# teensy_sync_rev1.net
KiCad netlist of a schematic drawn in EAGLE
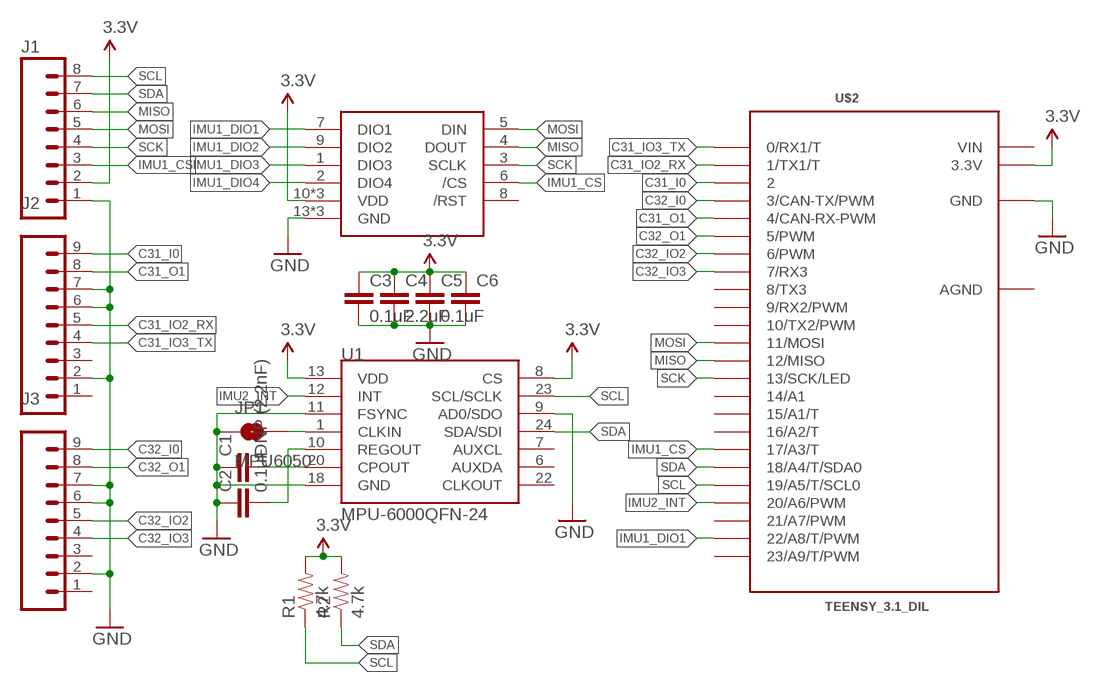
[diagram p0: schematic, sheet 1]

(export (version "E")
  (design (tool "Eeschema 10.0.6"))
  (components
    (comp (ref "C1")
      (value "DNP (2.2nF)")
      (footprint "eagle-import:0402-CAP")
      (libsource (lib "eagle-import") (part "CAP0402-CAP"))
    )
    (comp (ref "C2")
      (value "0.1uF")
      (footprint "eagle-import:0402-CAP")
      (libsource (lib "eagle-import") (part "CAP0402-CAP"))
    )
    (comp (ref "C3")
      (value "0.1uF")
      (footprint "eagle-import:0402-CAP")
      (libsource (lib "eagle-import") (part "CAP0402-CAP"))
    )
    (comp (ref "C4")
      (value "2.2uF")
      (footprint "eagle-import:0402-CAP")
      (libsource (lib "eagle-import") (part "CAP0402-CAP"))
    )
    (comp (ref "C5")
      (value "0.1uF")
      (footprint "eagle-import:0402-CAP")
      (libsource (lib "eagle-import") (part "CAP0402-CAP"))
    )
    (comp (ref "C6")
      (value "CAP0402-CAP")
      (footprint "eagle-import:0402-CAP")
      (libsource (lib "eagle-import") (part "CAP0402-CAP"))
    )
    (comp (ref "J1")
      (value "M08")
      (footprint "eagle-import:1X08_ROUND")
      (libsource (lib "eagle-import") (part "M08"))
    )
    (comp (ref "J2")
      (value "M09")
      (footprint "eagle-import:1X09")
      (libsource (lib "eagle-import") (part "M09"))
    )
    (comp (ref "J3")
      (value "M09")
      (footprint "eagle-import:1X09")
      (libsource (lib "eagle-import") (part "M09"))
    )
    (comp (ref "JP1")
      (value "MPU6050")
      (footprint "eagle-import:PAD-JUMPER-2-NO_YES_SILK")
      (libsource (lib "eagle-import") (part "JUMPER-PAD-2-NOYES_SILK"))
    )
    (comp (ref "R1")
      (value "4.7k")
      (footprint "eagle-import:0603-RES")
      (libsource (lib "eagle-import") (part "RESISTOR0603"))
    )
    (comp (ref "R2")
      (value "4.7k")
      (footprint "eagle-import:0603-RES")
      (libsource (lib "eagle-import") (part "RESISTOR0603"))
    )
    (comp (ref "U$1")
      (value "ADIS16448")
      (footprint "eagle-import:ADIS16448")
      (libsource (lib "eagle-import") (part "ADIS16448"))
    )
    (comp (ref "U$2")
      (value "TEENSY_3.1_DIL")
      (footprint "eagle-import:TEENSY3-DIL")
      (libsource (lib "eagle-import") (part "TEENSY_3.1_DIL"))
    )
    (comp (ref "U1")
      (value "MPU-6000QFN-24")
      (footprint "eagle-import:QFN-24-TESTING")
      (libsource (lib "eagle-import") (part "MPU-6000QFN-24"))
    )
  )
  (nets
    (net (code "1") (name "/AGND") (class "Default")
      (node (ref "U$2") (pin "AGND") (pinfunction "AGND_AGND") (pintype "power_in"))
    )
    (net (code "2") (name "/VIN") (class "Default")
      (node (ref "U$2") (pin "VIN") (pinfunction "VIN_VIN") (pintype "power_in"))
    )
    (net (code "3") (name "3.3V") (class "Default")
      (node (ref "C3") (pin "1") (pinfunction "1_1") (pintype "passive"))
      (node (ref "C4") (pin "1") (pinfunction "1_1") (pintype "passive"))
      (node (ref "C5") (pin "1") (pinfunction "1_1") (pintype "passive"))
      (node (ref "C6") (pin "1") (pinfunction "1_1") (pintype "passive"))
      (node (ref "J1") (pin "2") (pinfunction "2_2") (pintype "passive"))
      (node (ref "R1") (pin "2") (pinfunction "2_2") (pintype "passive"))
      (node (ref "R2") (pin "2") (pinfunction "2_2") (pintype "passive"))
      (node (ref "U$1") (pin "10") (pinfunction "VDD_10") (pintype "bidirectional"))
      (node (ref "U$1") (pin "11") (pinfunction "VDD_11") (pintype "bidirectional"))
      (node (ref "U$1") (pin "12") (pinfunction "VDD_12") (pintype "bidirectional"))
      (node (ref "U$2") (pin "3.3V") (pinfunction "3.3V_3.3V") (pintype "power_in"))
      (node (ref "U1") (pin "13") (pinfunction "VDD_13") (pintype "bidirectional"))
      (node (ref "U1") (pin "8") (pinfunction "CS_8") (pintype "bidirectional"))
    )
    (net (code "4") (name "C31_I0") (class "Default")
      (node (ref "J2") (pin "9") (pinfunction "9_9") (pintype "passive"))
      (node (ref "U$2") (pin "2") (pinfunction "2_2") (pintype "bidirectional"))
    )
    (net (code "5") (name "C31_IO2_RX") (class "Default")
      (node (ref "J2") (pin "5") (pinfunction "5_5") (pintype "passive"))
      (node (ref "U$2") (pin "1") (pinfunction "1/TX1/T_1") (pintype "bidirectional"))
    )
    (net (code "6") (name "C31_IO3_TX") (class "Default")
      (node (ref "J2") (pin "4") (pinfunction "4_4") (pintype "passive"))
      (node (ref "U$2") (pin "0") (pinfunction "0/RX1/T_0") (pintype "bidirectional"))
    )
    (net (code "7") (name "C31_O1") (class "Default")
      (node (ref "J2") (pin "8") (pinfunction "8_8") (pintype "passive"))
      (node (ref "U$2") (pin "4") (pinfunction "4/CAN-RX-PWM_4") (pintype "bidirectional"))
    )
    (net (code "8") (name "C32_I0") (class "Default")
      (node (ref "J3") (pin "9") (pinfunction "9_9") (pintype "passive"))
      (node (ref "U$2") (pin "3") (pinfunction "3/CAN-TX/PWM_3") (pintype "bidirectional"))
    )
    (net (code "9") (name "C32_IO2") (class "Default")
      (node (ref "J3") (pin "5") (pinfunction "5_5") (pintype "passive"))
      (node (ref "U$2") (pin "6") (pinfunction "6/PWM_6") (pintype "bidirectional"))
    )
    (net (code "10") (name "C32_IO3") (class "Default")
      (node (ref "J3") (pin "4") (pinfunction "4_4") (pintype "passive"))
      (node (ref "U$2") (pin "7") (pinfunction "7/RX3_7") (pintype "bidirectional"))
    )
    (net (code "11") (name "C32_O1") (class "Default")
      (node (ref "J3") (pin "8") (pinfunction "8_8") (pintype "passive"))
      (node (ref "U$2") (pin "5") (pinfunction "5/PWM_5") (pintype "bidirectional"))
    )
    (net (code "12") (name "GND") (class "Default")
      (node (ref "C1") (pin "1") (pinfunction "1_1") (pintype "passive"))
      (node (ref "C2") (pin "1") (pinfunction "1_1") (pintype "passive"))
      (node (ref "C3") (pin "2") (pinfunction "2_2") (pintype "passive"))
      (node (ref "C4") (pin "2") (pinfunction "2_2") (pintype "passive"))
      (node (ref "C5") (pin "2") (pinfunction "2_2") (pintype "passive"))
      (node (ref "C6") (pin "2") (pinfunction "2_2") (pintype "passive"))
      (node (ref "J1") (pin "1") (pinfunction "1_1") (pintype "passive"))
      (node (ref "J2") (pin "2") (pinfunction "2_2") (pintype "passive"))
      (node (ref "J2") (pin "6") (pinfunction "6_6") (pintype "passive"))
      (node (ref "J2") (pin "7") (pinfunction "7_7") (pintype "passive"))
      (node (ref "J3") (pin "2") (pinfunction "2_2") (pintype "passive"))
      (node (ref "J3") (pin "6") (pinfunction "6_6") (pintype "passive"))
      (node (ref "J3") (pin "7") (pinfunction "7_7") (pintype "passive"))
      (node (ref "JP1") (pin "1") (pinfunction "1_1") (pintype "passive"))
      (node (ref "U$1") (pin "13") (pinfunction "GND_13") (pintype "bidirectional"))
      (node (ref "U$1") (pin "14") (pinfunction "GND_14") (pintype "bidirectional"))
      (node (ref "U$1") (pin "15") (pinfunction "GND_15") (pintype "bidirectional"))
      (node (ref "U$2") (pin "GND") (pinfunction "GND_GND") (pintype "power_in"))
      (node (ref "U1") (pin "11") (pinfunction "FSYNC_11") (pintype "bidirectional"))
      (node (ref "U1") (pin "18") (pinfunction "GND_18") (pintype "bidirectional"))
      (node (ref "U1") (pin "9") (pinfunction "AD0/SDO_9") (pintype "bidirectional"))
    )
    (net (code "13") (name "IMU1_CS") (class "Default")
      (node (ref "J1") (pin "3") (pinfunction "3_3") (pintype "passive"))
      (node (ref "U$1") (pin "6") (pinfunction "/CS_6") (pintype "bidirectional"))
      (node (ref "U$2") (pin "17/A3") (pinfunction "17/A3/T_17/A3") (pintype "bidirectional"))
    )
    (net (code "14") (name "IMU1_DIO1") (class "Default")
      (node (ref "U$1") (pin "7") (pinfunction "DIO1_7") (pintype "bidirectional"))
      (node (ref "U$2") (pin "22/A8") (pinfunction "22/A8/T/PWM_22/A8") (pintype "bidirectional"))
    )
    (net (code "15") (name "IMU1_DIO2") (class "Default")
      (node (ref "U$1") (pin "9") (pinfunction "DIO2_9") (pintype "bidirectional"))
    )
    (net (code "16") (name "IMU1_DIO3") (class "Default")
      (node (ref "U$1") (pin "1") (pinfunction "DIO3_1") (pintype "bidirectional"))
    )
    (net (code "17") (name "IMU1_DIO4") (class "Default")
      (node (ref "U$1") (pin "2") (pinfunction "DIO4_2") (pintype "bidirectional"))
    )
    (net (code "18") (name "IMU2_INT") (class "Default")
      (node (ref "U$2") (pin "20/A6") (pinfunction "20/A6/PWM_20/A6") (pintype "bidirectional"))
      (node (ref "U1") (pin "12") (pinfunction "INT_12") (pintype "bidirectional"))
    )
    (net (code "19") (name "MISO") (class "Default")
      (node (ref "J1") (pin "6") (pinfunction "6_6") (pintype "passive"))
      (node (ref "U$1") (pin "4") (pinfunction "DOUT_4") (pintype "bidirectional"))
      (node (ref "U$2") (pin "12") (pinfunction "12/MISO_12") (pintype "bidirectional"))
    )
    (net (code "20") (name "MOSI") (class "Default")
      (node (ref "J1") (pin "5") (pinfunction "5_5") (pintype "passive"))
      (node (ref "U$1") (pin "5") (pinfunction "DIN_5") (pintype "bidirectional"))
      (node (ref "U$2") (pin "11") (pinfunction "11/MOSI_11") (pintype "bidirectional"))
    )
    (net (code "21") (name "Net-(U1-CLKIN)") (class "Default")
      (node (ref "JP1") (pin "2") (pinfunction "2_2") (pintype "passive"))
      (node (ref "U1") (pin "1") (pinfunction "CLKIN_1") (pintype "bidirectional"))
    )
    (net (code "22") (name "Net-(U1-CPOUT)") (class "Default")
      (node (ref "C1") (pin "2") (pinfunction "2_2") (pintype "passive"))
      (node (ref "U1") (pin "20") (pinfunction "CPOUT_20") (pintype "bidirectional"))
    )
    (net (code "23") (name "Net-(U1-REGOUT)") (class "Default")
      (node (ref "C2") (pin "2") (pinfunction "2_2") (pintype "passive"))
      (node (ref "U1") (pin "10") (pinfunction "REGOUT_10") (pintype "bidirectional"))
    )
    (net (code "24") (name "SCK") (class "Default")
      (node (ref "J1") (pin "4") (pinfunction "4_4") (pintype "passive"))
      (node (ref "U$1") (pin "3") (pinfunction "SCLK_3") (pintype "bidirectional"))
      (node (ref "U$2") (pin "13") (pinfunction "13/SCK/LED_13") (pintype "bidirectional"))
    )
    (net (code "25") (name "SCL") (class "Default")
      (node (ref "J1") (pin "8") (pinfunction "8_8") (pintype "passive"))
      (node (ref "R1") (pin "1") (pinfunction "1_1") (pintype "passive"))
      (node (ref "U$2") (pin "19/A5") (pinfunction "19/A5/T/SCL0_19/A5") (pintype "bidirectional"))
      (node (ref "U1") (pin "23") (pinfunction "SCL/SCLK_23") (pintype "bidirectional"))
    )
    (net (code "26") (name "SDA") (class "Default")
      (node (ref "J1") (pin "7") (pinfunction "7_7") (pintype "passive"))
      (node (ref "R2") (pin "1") (pinfunction "1_1") (pintype "passive"))
      (node (ref "U$2") (pin "18/A4") (pinfunction "18/A4/T/SDA0_18/A4") (pintype "bidirectional"))
      (node (ref "U1") (pin "24") (pinfunction "SDA/SDI_24") (pintype "bidirectional"))
    )
    (net (code "27") (name "unconnected-(J2-Pad1)") (class "Default")
      (node (ref "J2") (pin "1") (pinfunction "1_1") (pintype "passive"))
    )
    (net (code "28") (name "unconnected-(J2-Pad3)") (class "Default")
      (node (ref "J2") (pin "3") (pinfunction "3_3") (pintype "passive"))
    )
    (net (code "29") (name "unconnected-(J3-Pad1)") (class "Default")
      (node (ref "J3") (pin "1") (pinfunction "1_1") (pintype "passive"))
    )
    (net (code "30") (name "unconnected-(J3-Pad3)") (class "Default")
      (node (ref "J3") (pin "3") (pinfunction "3_3") (pintype "passive"))
    )
    (net (code "31") (name "unconnected-(U$1-{slash}RST-Pad8)") (class "Default")
      (node (ref "U$1") (pin "8") (pinfunction "/RST_8") (pintype "bidirectional"))
    )
    (net (code "32") (name "unconnected-(U$2-8{slash}TX3-Pad8)") (class "Default")
      (node (ref "U$2") (pin "8") (pinfunction "8/TX3_8") (pintype "bidirectional"))
    )
    (net (code "33") (name "unconnected-(U$2-9{slash}RX2{slash}PWM-Pad9)") (class "Default")
      (node (ref "U$2") (pin "9") (pinfunction "9/RX2/PWM_9") (pintype "bidirectional"))
    )
    (net (code "34") (name "unconnected-(U$2-10{slash}TX2{slash}PWM-Pad10)") (class "Default")
      (node (ref "U$2") (pin "10") (pinfunction "10/TX2/PWM_10") (pintype "bidirectional"))
    )
    (net (code "35") (name "unconnected-(U$2-14{slash}A1-Pad14{slash}A0)") (class "Default")
      (node (ref "U$2") (pin "14/A0") (pinfunction "14/A1_14/A0") (pintype "bidirectional"))
    )
    (net (code "36") (name "unconnected-(U$2-15{slash}A1{slash}T-Pad15{slash}A1)") (class "Default")
      (node (ref "U$2") (pin "15/A1") (pinfunction "15/A1/T_15/A1") (pintype "bidirectional"))
    )
    (net (code "37") (name "unconnected-(U$2-16{slash}A2{slash}T-Pad16{slash}A2)") (class "Default")
      (node (ref "U$2") (pin "16/A2") (pinfunction "16/A2/T_16/A2") (pintype "bidirectional"))
    )
    (net (code "38") (name "unconnected-(U$2-21{slash}A7{slash}PWM-Pad21{slash}A7)") (class "Default")
      (node (ref "U$2") (pin "21/A7") (pinfunction "21/A7/PWM_21/A7") (pintype "bidirectional"))
    )
    (net (code "39") (name "unconnected-(U$2-23{slash}A9{slash}T{slash}PWM-Pad23{slash}A9)") (class "Default")
      (node (ref "U$2") (pin "23/A9") (pinfunction "23/A9/T/PWM_23/A9") (pintype "bidirectional"))
    )
    (net (code "40") (name "unconnected-(U1-AUXCL-Pad7)") (class "Default")
      (node (ref "U1") (pin "7") (pinfunction "AUXCL_7") (pintype "bidirectional"))
    )
    (net (code "41") (name "unconnected-(U1-AUXDA-Pad6)") (class "Default")
      (node (ref "U1") (pin "6") (pinfunction "AUXDA_6") (pintype "bidirectional"))
    )
    (net (code "42") (name "unconnected-(U1-CLKOUT-Pad22)") (class "Default")
      (node (ref "U1") (pin "22") (pinfunction "CLKOUT_22") (pintype "bidirectional"))
    )
  )
)
